# Sheet2.net
KiCad netlist of a schematic drawn in Altium Designer
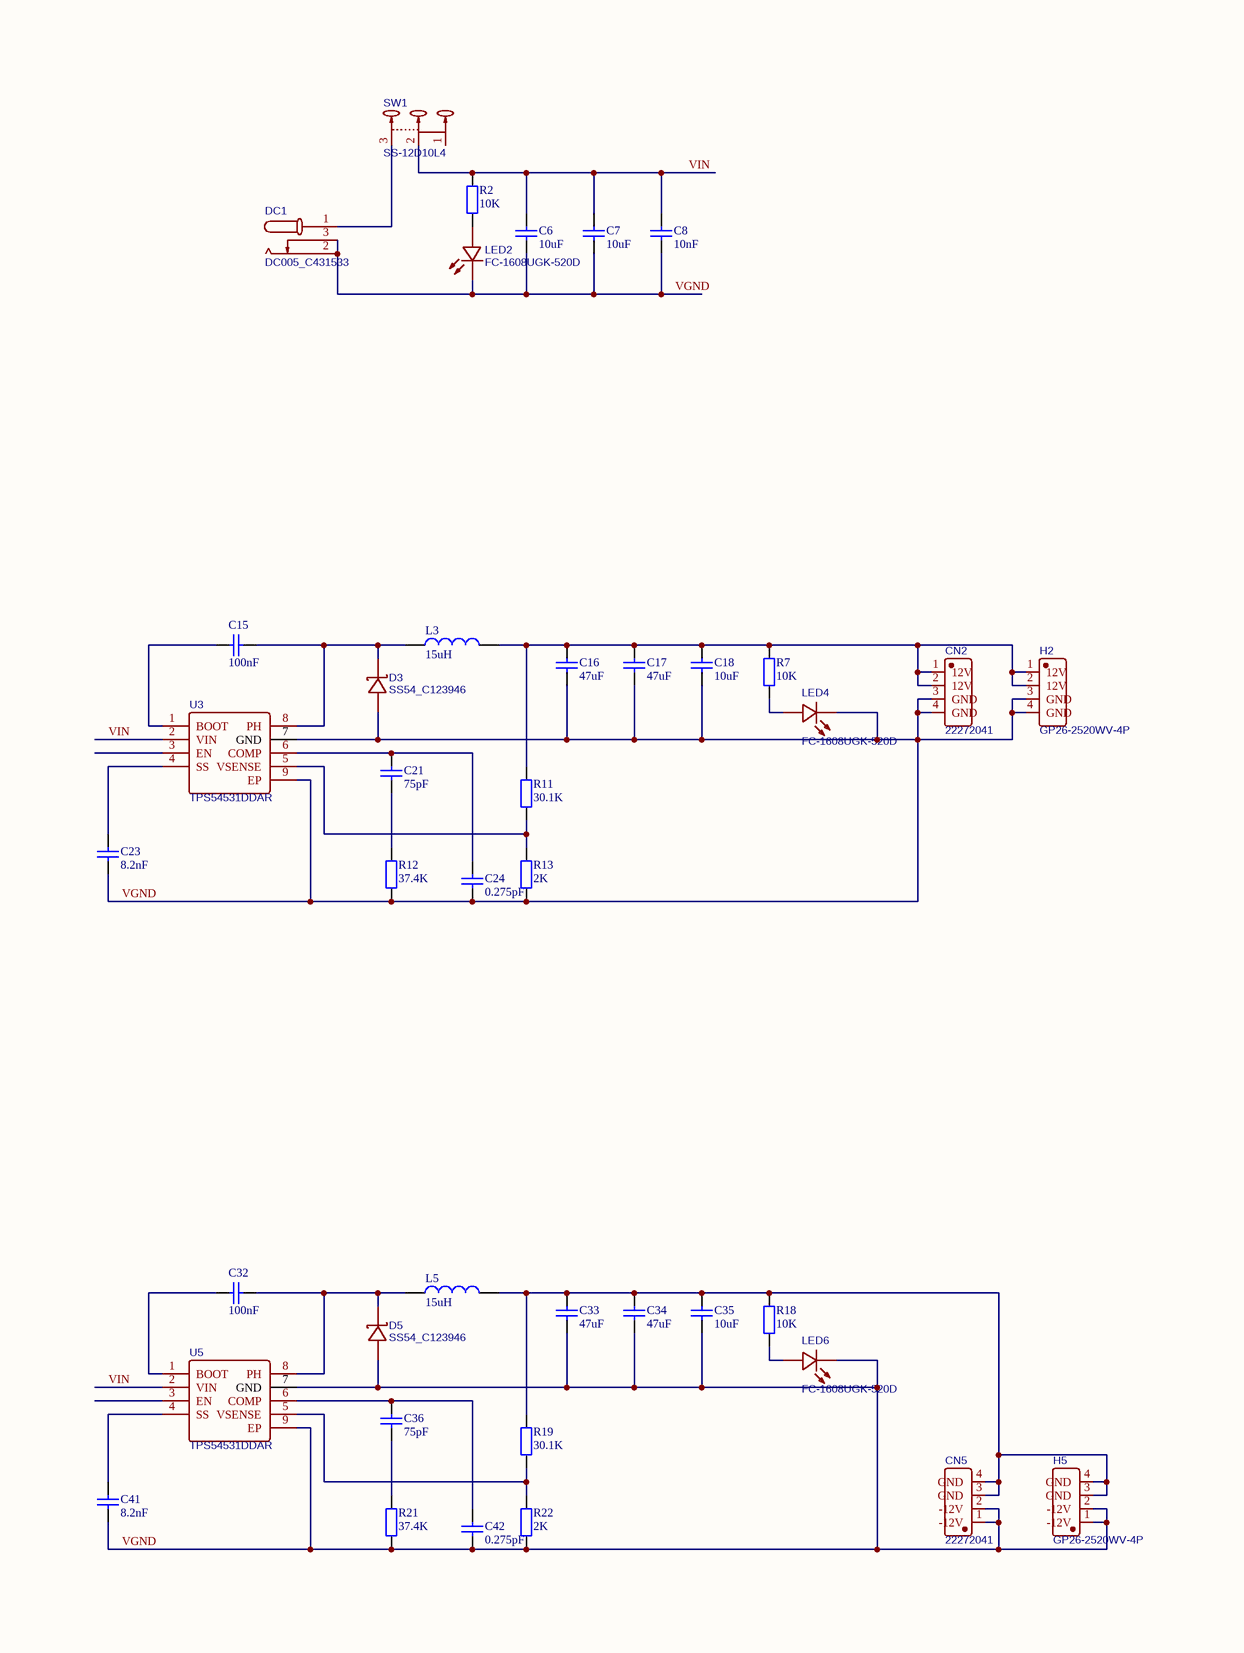
[diagram p0: Sheet2.SchDoc, left]
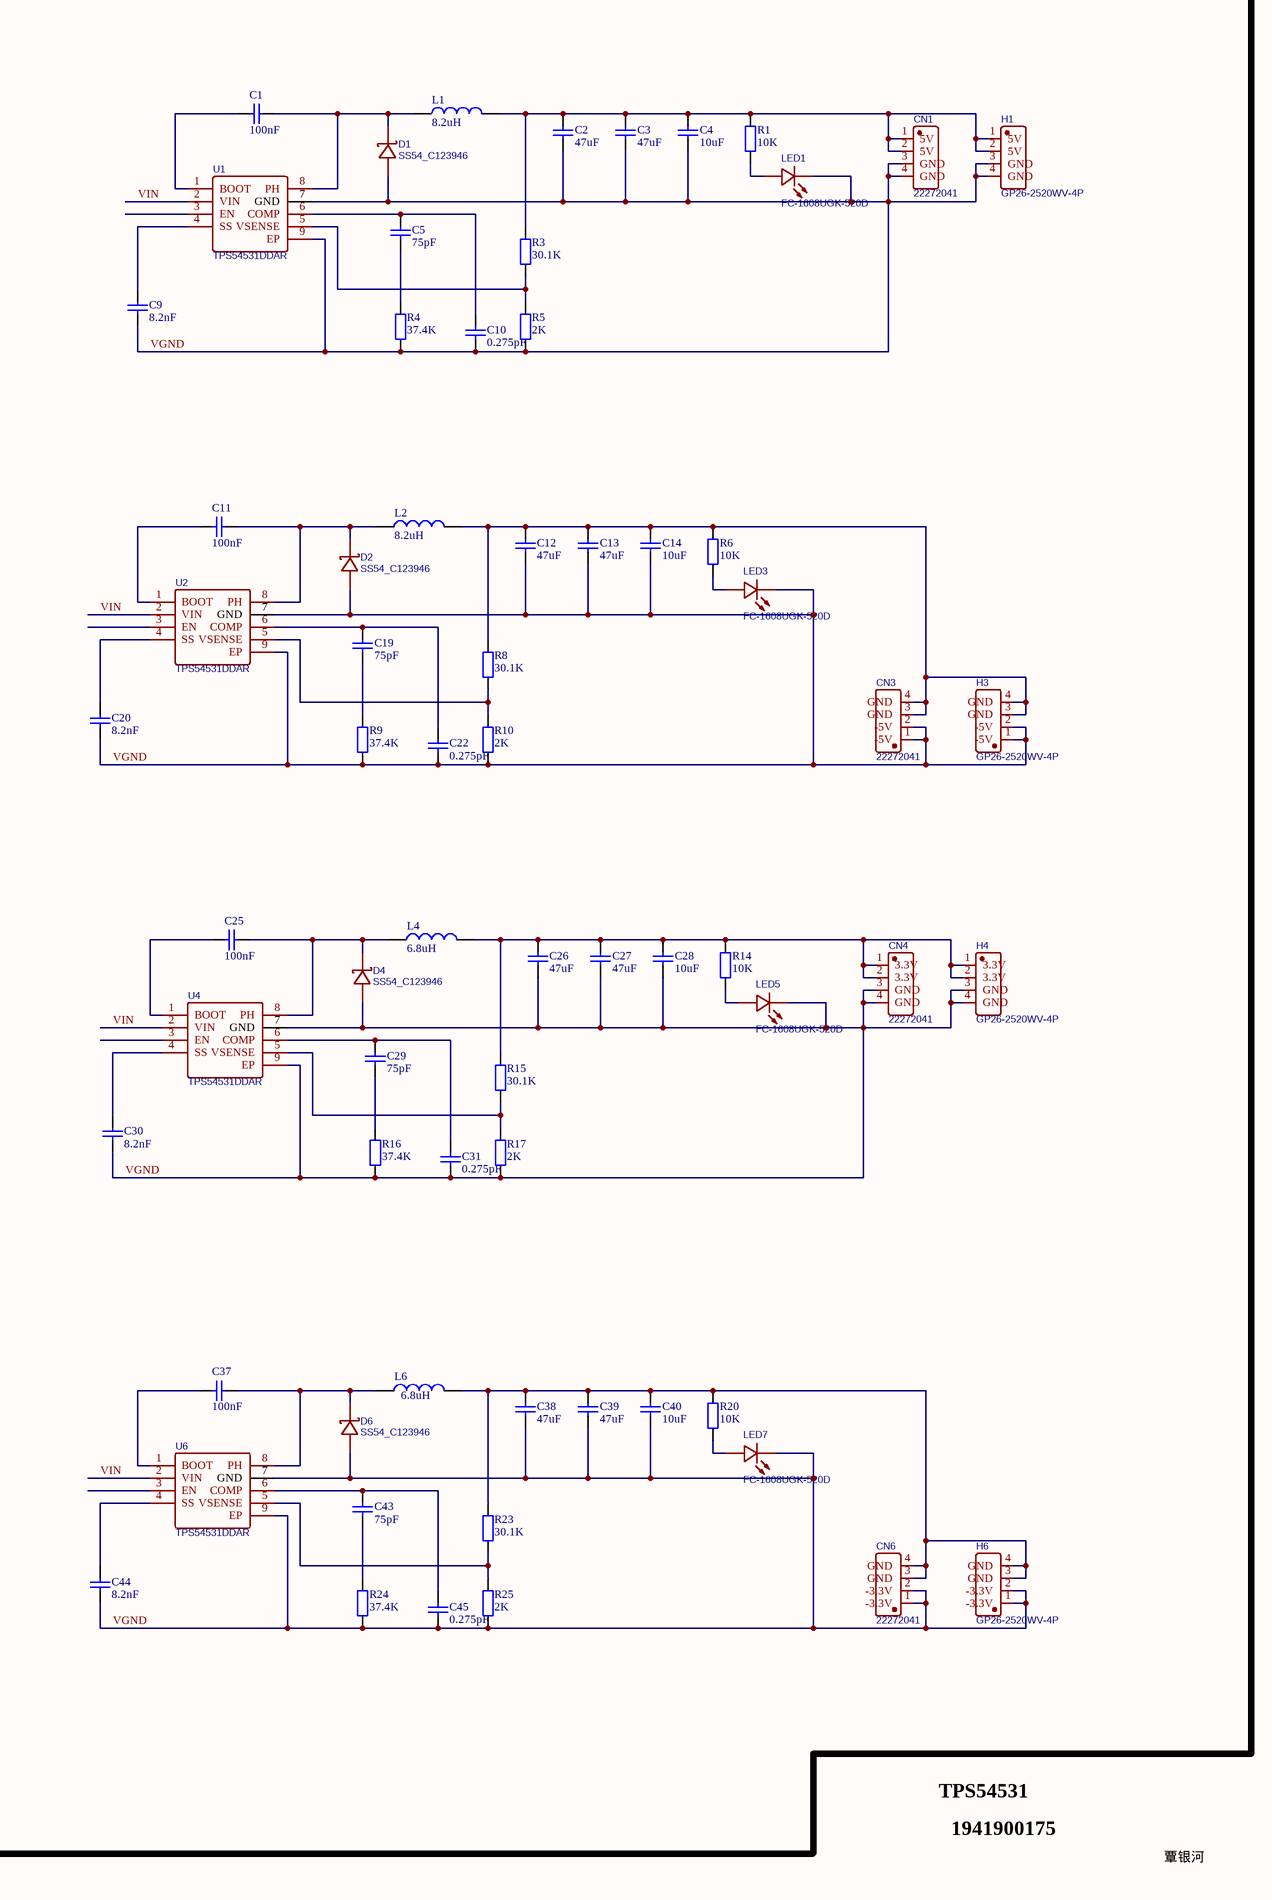
[diagram p1: Sheet2.SchDoc, right]

(export (version "E")
  (design (tool "Eeschema 10.0.6"))
  (components
    (comp (ref "C1")
      (value "100nF")
      (footprint "C0603_M")
      (description "贴片电容")
      (libsource (lib "0.1 - 电阻-电容-电感-磁珠-电位器") (part "C"))
    )
    (comp (ref "C2")
      (value "47uF")
      (footprint "C0603_M")
      (description "贴片电容")
      (libsource (lib "0.1 - 电阻-电容-电感-磁珠-电位器") (part "C"))
    )
    (comp (ref "C3")
      (value "47uF")
      (footprint "C0603_M")
      (description "贴片电容")
      (libsource (lib "0.1 - 电阻-电容-电感-磁珠-电位器") (part "C"))
    )
    (comp (ref "C4")
      (value "10uF")
      (footprint "C0603_M")
      (description "贴片电容")
      (libsource (lib "0.1 - 电阻-电容-电感-磁珠-电位器") (part "C"))
    )
    (comp (ref "C5")
      (value "75pF")
      (footprint "C0603_M")
      (description "贴片电容")
      (libsource (lib "0.1 - 电阻-电容-电感-磁珠-电位器") (part "C"))
    )
    (comp (ref "C6")
      (value "10uF")
      (footprint "C0603_M")
      (description "贴片电容")
      (libsource (lib "0.1 - 电阻-电容-电感-磁珠-电位器") (part "C"))
    )
    (comp (ref "C7")
      (value "10uF")
      (footprint "C0603_M")
      (description "贴片电容")
      (libsource (lib "0.1 - 电阻-电容-电感-磁珠-电位器") (part "C"))
    )
    (comp (ref "C8")
      (value "10nF")
      (footprint "C0603_M")
      (description "贴片电容")
      (libsource (lib "0.1 - 电阻-电容-电感-磁珠-电位器") (part "C"))
    )
    (comp (ref "C9")
      (value "8.2nF")
      (footprint "C0603_M")
      (description "贴片电容")
      (libsource (lib "0.1 - 电阻-电容-电感-磁珠-电位器") (part "C"))
    )
    (comp (ref "C10")
      (value "0.275pF")
      (footprint "C0603_M")
      (description "贴片电容")
      (libsource (lib "0.1 - 电阻-电容-电感-磁珠-电位器") (part "C"))
    )
    (comp (ref "C11")
      (value "100nF")
      (footprint "C0603_M")
      (description "贴片电容")
      (libsource (lib "0.1 - 电阻-电容-电感-磁珠-电位器") (part "C"))
    )
    (comp (ref "C12")
      (value "47uF")
      (footprint "C0603_M")
      (description "贴片电容")
      (libsource (lib "0.1 - 电阻-电容-电感-磁珠-电位器") (part "C"))
    )
    (comp (ref "C13")
      (value "47uF")
      (footprint "C0603_M")
      (description "贴片电容")
      (libsource (lib "0.1 - 电阻-电容-电感-磁珠-电位器") (part "C"))
    )
    (comp (ref "C14")
      (value "10uF")
      (footprint "C0603_M")
      (description "贴片电容")
      (libsource (lib "0.1 - 电阻-电容-电感-磁珠-电位器") (part "C"))
    )
    (comp (ref "C15")
      (value "100nF")
      (footprint "C0603_M")
      (description "贴片电容")
      (libsource (lib "0.1 - 电阻-电容-电感-磁珠-电位器") (part "C"))
    )
    (comp (ref "C16")
      (value "47uF")
      (footprint "C0603_M")
      (description "贴片电容")
      (libsource (lib "0.1 - 电阻-电容-电感-磁珠-电位器") (part "C"))
    )
    (comp (ref "C17")
      (value "47uF")
      (footprint "C0603_M")
      (description "贴片电容")
      (libsource (lib "0.1 - 电阻-电容-电感-磁珠-电位器") (part "C"))
    )
    (comp (ref "C18")
      (value "10uF")
      (footprint "C0603_M")
      (description "贴片电容")
      (libsource (lib "0.1 - 电阻-电容-电感-磁珠-电位器") (part "C"))
    )
    (comp (ref "C19")
      (value "75pF")
      (footprint "C0603_M")
      (description "贴片电容")
      (libsource (lib "0.1 - 电阻-电容-电感-磁珠-电位器") (part "C"))
    )
    (comp (ref "C20")
      (value "8.2nF")
      (footprint "C0603_M")
      (description "贴片电容")
      (libsource (lib "0.1 - 电阻-电容-电感-磁珠-电位器") (part "C"))
    )
    (comp (ref "C21")
      (value "75pF")
      (footprint "C0603_M")
      (description "贴片电容")
      (libsource (lib "0.1 - 电阻-电容-电感-磁珠-电位器") (part "C"))
    )
    (comp (ref "C22")
      (value "0.275pF")
      (footprint "C0603_M")
      (description "贴片电容")
      (libsource (lib "0.1 - 电阻-电容-电感-磁珠-电位器") (part "C"))
    )
    (comp (ref "C23")
      (value "8.2nF")
      (footprint "C0603_M")
      (description "贴片电容")
      (libsource (lib "0.1 - 电阻-电容-电感-磁珠-电位器") (part "C"))
    )
    (comp (ref "C24")
      (value "0.275pF")
      (footprint "C0603_M")
      (description "贴片电容")
      (libsource (lib "0.1 - 电阻-电容-电感-磁珠-电位器") (part "C"))
    )
    (comp (ref "C25")
      (value "100nF")
      (footprint "C0603_M")
      (description "贴片电容")
      (libsource (lib "0.1 - 电阻-电容-电感-磁珠-电位器") (part "C"))
    )
    (comp (ref "C26")
      (value "47uF")
      (footprint "C0603_M")
      (description "贴片电容")
      (libsource (lib "0.1 - 电阻-电容-电感-磁珠-电位器") (part "C"))
    )
    (comp (ref "C27")
      (value "47uF")
      (footprint "C0603_M")
      (description "贴片电容")
      (libsource (lib "0.1 - 电阻-电容-电感-磁珠-电位器") (part "C"))
    )
    (comp (ref "C28")
      (value "10uF")
      (footprint "C0603_M")
      (description "贴片电容")
      (libsource (lib "0.1 - 电阻-电容-电感-磁珠-电位器") (part "C"))
    )
    (comp (ref "C29")
      (value "75pF")
      (footprint "C0603_M")
      (description "贴片电容")
      (libsource (lib "0.1 - 电阻-电容-电感-磁珠-电位器") (part "C"))
    )
    (comp (ref "C30")
      (value "8.2nF")
      (footprint "C0603_M")
      (description "贴片电容")
      (libsource (lib "0.1 - 电阻-电容-电感-磁珠-电位器") (part "C"))
    )
    (comp (ref "C31")
      (value "0.275pF")
      (footprint "C0603_M")
      (description "贴片电容")
      (libsource (lib "0.1 - 电阻-电容-电感-磁珠-电位器") (part "C"))
    )
    (comp (ref "C32")
      (value "100nF")
      (footprint "C0603_M")
      (description "贴片电容")
      (libsource (lib "0.1 - 电阻-电容-电感-磁珠-电位器") (part "C"))
    )
    (comp (ref "C33")
      (value "47uF")
      (footprint "C0603_M")
      (description "贴片电容")
      (libsource (lib "0.1 - 电阻-电容-电感-磁珠-电位器") (part "C"))
    )
    (comp (ref "C34")
      (value "47uF")
      (footprint "C0603_M")
      (description "贴片电容")
      (libsource (lib "0.1 - 电阻-电容-电感-磁珠-电位器") (part "C"))
    )
    (comp (ref "C35")
      (value "10uF")
      (footprint "C0603_M")
      (description "贴片电容")
      (libsource (lib "0.1 - 电阻-电容-电感-磁珠-电位器") (part "C"))
    )
    (comp (ref "C36")
      (value "75pF")
      (footprint "C0603_M")
      (description "贴片电容")
      (libsource (lib "0.1 - 电阻-电容-电感-磁珠-电位器") (part "C"))
    )
    (comp (ref "C37")
      (value "100nF")
      (footprint "C0603_M")
      (description "贴片电容")
      (libsource (lib "0.1 - 电阻-电容-电感-磁珠-电位器") (part "C"))
    )
    (comp (ref "C38")
      (value "47uF")
      (footprint "C0603_M")
      (description "贴片电容")
      (libsource (lib "0.1 - 电阻-电容-电感-磁珠-电位器") (part "C"))
    )
    (comp (ref "C39")
      (value "47uF")
      (footprint "C0603_M")
      (description "贴片电容")
      (libsource (lib "0.1 - 电阻-电容-电感-磁珠-电位器") (part "C"))
    )
    (comp (ref "C40")
      (value "10uF")
      (footprint "C0603_M")
      (description "贴片电容")
      (libsource (lib "0.1 - 电阻-电容-电感-磁珠-电位器") (part "C"))
    )
    (comp (ref "C41")
      (value "8.2nF")
      (footprint "C0603_M")
      (description "贴片电容")
      (libsource (lib "0.1 - 电阻-电容-电感-磁珠-电位器") (part "C"))
    )
    (comp (ref "C42")
      (value "0.275pF")
      (footprint "C0603_M")
      (description "贴片电容")
      (libsource (lib "0.1 - 电阻-电容-电感-磁珠-电位器") (part "C"))
    )
    (comp (ref "C43")
      (value "75pF")
      (footprint "C0603_M")
      (description "贴片电容")
      (libsource (lib "0.1 - 电阻-电容-电感-磁珠-电位器") (part "C"))
    )
    (comp (ref "C44")
      (value "8.2nF")
      (footprint "C0603_M")
      (description "贴片电容")
      (libsource (lib "0.1 - 电阻-电容-电感-磁珠-电位器") (part "C"))
    )
    (comp (ref "C45")
      (value "0.275pF")
      (footprint "C0603_M")
      (description "贴片电容")
      (libsource (lib "0.1 - 电阻-电容-电感-磁珠-电位器") (part "C"))
    )
    (comp (ref "CN1")
      (value "22272041")
      (footprint "CONN-TH_22272041")
      (fields (field (name "BOM_SUPPLIER PART") "C504991") (field (name "CONTRIBUTOR") "LCSC"))
      (libsource (lib "22272041") (part "22272041"))
    )
    (comp (ref "CN2")
      (value "22272041")
      (footprint "CONN-TH_22272041")
      (fields (field (name "BOM_SUPPLIER PART") "C504991") (field (name "CONTRIBUTOR") "LCSC"))
      (libsource (lib "22272041") (part "22272041"))
    )
    (comp (ref "CN3")
      (value "22272041")
      (footprint "CONN-TH_22272041")
      (fields (field (name "BOM_SUPPLIER PART") "C504991") (field (name "CONTRIBUTOR") "LCSC"))
      (libsource (lib "22272041") (part "22272041"))
    )
    (comp (ref "CN4")
      (value "22272041")
      (footprint "CONN-TH_22272041")
      (fields (field (name "BOM_SUPPLIER PART") "C504991") (field (name "CONTRIBUTOR") "LCSC"))
      (libsource (lib "22272041") (part "22272041"))
    )
    (comp (ref "CN5")
      (value "22272041")
      (footprint "CONN-TH_22272041")
      (fields (field (name "BOM_SUPPLIER PART") "C504991") (field (name "CONTRIBUTOR") "LCSC"))
      (libsource (lib "22272041") (part "22272041"))
    )
    (comp (ref "CN6")
      (value "22272041")
      (footprint "CONN-TH_22272041")
      (fields (field (name "BOM_SUPPLIER PART") "C504991") (field (name "CONTRIBUTOR") "LCSC"))
      (libsource (lib "22272041") (part "22272041"))
    )
    (comp (ref "D1")
      (value "SS54_C123946")
      (footprint "SMA_L4.4-W2.8-LS5.4-RD")
      (fields
        (field (name "BOM_SUPPLIER PART") "C123946")
        (field (name "BOM_MANUFACTURER PART") "SS54")
        (field (name "CONTRIBUTOR") "LCSC")
      )
      (libsource (lib "ss54 C123946") (part "SS54_C123946"))
    )
    (comp (ref "D2")
      (value "SS54_C123946")
      (footprint "SMA_L4.4-W2.8-LS5.4-RD")
      (fields
        (field (name "BOM_SUPPLIER PART") "C123946")
        (field (name "BOM_MANUFACTURER PART") "SS54")
        (field (name "CONTRIBUTOR") "LCSC")
      )
      (libsource (lib "ss54 C123946") (part "SS54_C123946"))
    )
    (comp (ref "D3")
      (value "SS54_C123946")
      (footprint "SMA_L4.4-W2.8-LS5.4-RD")
      (fields
        (field (name "BOM_SUPPLIER PART") "C123946")
        (field (name "BOM_MANUFACTURER PART") "SS54")
        (field (name "CONTRIBUTOR") "LCSC")
      )
      (libsource (lib "ss54 C123946") (part "SS54_C123946"))
    )
    (comp (ref "D4")
      (value "SS54_C123946")
      (footprint "SMA_L4.4-W2.8-LS5.4-RD")
      (fields
        (field (name "BOM_SUPPLIER PART") "C123946")
        (field (name "BOM_MANUFACTURER PART") "SS54")
        (field (name "CONTRIBUTOR") "LCSC")
      )
      (libsource (lib "ss54 C123946") (part "SS54_C123946"))
    )
    (comp (ref "D5")
      (value "SS54_C123946")
      (footprint "SMA_L4.4-W2.8-LS5.4-RD")
      (fields
        (field (name "BOM_SUPPLIER PART") "C123946")
        (field (name "BOM_MANUFACTURER PART") "SS54")
        (field (name "CONTRIBUTOR") "LCSC")
      )
      (libsource (lib "ss54 C123946") (part "SS54_C123946"))
    )
    (comp (ref "D6")
      (value "SS54_C123946")
      (footprint "SMA_L4.4-W2.8-LS5.4-RD")
      (fields
        (field (name "BOM_SUPPLIER PART") "C123946")
        (field (name "BOM_MANUFACTURER PART") "SS54")
        (field (name "CONTRIBUTOR") "LCSC")
      )
      (libsource (lib "ss54 C123946") (part "SS54_C123946"))
    )
    (comp (ref "DC1")
      (value "DC005_C431533")
      (footprint "DC-IN-TH_DC005")
      (fields
        (field (name "BOM_SUPPLIER PART") "C431533")
        (field (name "BOM_MANUFACTURER PART") "DC005")
        (field (name "CONTRIBUTOR") "LCSC")
      )
      (libsource (lib "DC005") (part "DC005_C431533"))
    )
    (comp (ref "H1")
      (value "GP26-2520WV-4P")
      (footprint "HDR-TH_4P-P2.54-V-F-R1-C4")
      (fields (field (name "BOM_SUPPLIER PART") "C2681739") (field (name "CONTRIBUTOR") "LCSC"))
      (libsource (lib "gp26-2520wv-4p") (part "GP26-2520WV-4P"))
    )
    (comp (ref "H2")
      (value "GP26-2520WV-4P")
      (footprint "HDR-TH_4P-P2.54-V-F-R1-C4")
      (fields (field (name "BOM_SUPPLIER PART") "C2681739") (field (name "CONTRIBUTOR") "LCSC"))
      (libsource (lib "gp26-2520wv-4p") (part "GP26-2520WV-4P"))
    )
    (comp (ref "H3")
      (value "GP26-2520WV-4P")
      (footprint "HDR-TH_4P-P2.54-V-F-R1-C4")
      (fields (field (name "BOM_SUPPLIER PART") "C2681739") (field (name "CONTRIBUTOR") "LCSC"))
      (libsource (lib "gp26-2520wv-4p") (part "GP26-2520WV-4P"))
    )
    (comp (ref "H4")
      (value "GP26-2520WV-4P")
      (footprint "HDR-TH_4P-P2.54-V-F-R1-C4")
      (fields (field (name "BOM_SUPPLIER PART") "C2681739") (field (name "CONTRIBUTOR") "LCSC"))
      (libsource (lib "gp26-2520wv-4p") (part "GP26-2520WV-4P"))
    )
    (comp (ref "H5")
      (value "GP26-2520WV-4P")
      (footprint "HDR-TH_4P-P2.54-V-F-R1-C4")
      (fields (field (name "BOM_SUPPLIER PART") "C2681739") (field (name "CONTRIBUTOR") "LCSC"))
      (libsource (lib "gp26-2520wv-4p") (part "GP26-2520WV-4P"))
    )
    (comp (ref "H6")
      (value "GP26-2520WV-4P")
      (footprint "HDR-TH_4P-P2.54-V-F-R1-C4")
      (fields (field (name "BOM_SUPPLIER PART") "C2681739") (field (name "CONTRIBUTOR") "LCSC"))
      (libsource (lib "gp26-2520wv-4p") (part "GP26-2520WV-4P"))
    )
    (comp (ref "L1")
      (value "8.2uH")
      (footprint "IND-SMD_L7.0-W6.6")
      (description "色环电感")
      (libsource (lib "0.1 - 电阻-电容-电感-磁珠-电位器") (part "L-AL"))
    )
    (comp (ref "L2")
      (value "8.2uH")
      (footprint "IND-SMD_L7.0-W6.6")
      (description "色环电感")
      (libsource (lib "0.1 - 电阻-电容-电感-磁珠-电位器") (part "L-AL"))
    )
    (comp (ref "L3")
      (value "15uH")
      (footprint "IND-SMD_L5.0-W5.0_SWPA5040S")
      (description "色环电感")
      (libsource (lib "0.1 - 电阻-电容-电感-磁珠-电位器") (part "L-AL"))
    )
    (comp (ref "L4")
      (value "6.8uH")
      (footprint "IND-SMD_L10.5-W10.3")
      (description "色环电感")
      (libsource (lib "0.1 - 电阻-电容-电感-磁珠-电位器") (part "L-AL"))
    )
    (comp (ref "L5")
      (value "15uH")
      (footprint "IND-SMD_L5.0-W5.0_SWPA5040S")
      (description "色环电感")
      (libsource (lib "0.1 - 电阻-电容-电感-磁珠-电位器") (part "L-AL"))
    )
    (comp (ref "L6")
      (value "6.8uH")
      (footprint "IND-SMD_L10.5-W10.3")
      (description "色环电感")
      (libsource (lib "0.1 - 电阻-电容-电感-磁珠-电位器") (part "L-AL"))
    )
    (comp (ref "LED1")
      (value "FC-1608UGK-520D")
      (footprint "LED0603-RD")
      (fields (field (name "BOM_SUPPLIER PART") "C87326"))
      (libsource (lib "fc-1608ugk-520d") (part "FC-1608UGK-520D"))
    )
    (comp (ref "LED2")
      (value "FC-1608UGK-520D")
      (footprint "LED0603-RD")
      (fields (field (name "BOM_SUPPLIER PART") "C87326"))
      (libsource (lib "fc-1608ugk-520d") (part "FC-1608UGK-520D"))
    )
    (comp (ref "LED3")
      (value "FC-1608UGK-520D")
      (footprint "LED0603-RD")
      (fields (field (name "BOM_SUPPLIER PART") "C87326"))
      (libsource (lib "fc-1608ugk-520d") (part "FC-1608UGK-520D"))
    )
    (comp (ref "LED4")
      (value "FC-1608UGK-520D")
      (footprint "LED0603-RD")
      (fields (field (name "BOM_SUPPLIER PART") "C87326"))
      (libsource (lib "fc-1608ugk-520d") (part "FC-1608UGK-520D"))
    )
    (comp (ref "LED5")
      (value "FC-1608UGK-520D")
      (footprint "LED0603-RD")
      (fields (field (name "BOM_SUPPLIER PART") "C87326"))
      (libsource (lib "fc-1608ugk-520d") (part "FC-1608UGK-520D"))
    )
    (comp (ref "LED6")
      (value "FC-1608UGK-520D")
      (footprint "LED0603-RD")
      (fields (field (name "BOM_SUPPLIER PART") "C87326"))
      (libsource (lib "fc-1608ugk-520d") (part "FC-1608UGK-520D"))
    )
    (comp (ref "LED7")
      (value "FC-1608UGK-520D")
      (footprint "LED0603-RD")
      (fields (field (name "BOM_SUPPLIER PART") "C87326"))
      (libsource (lib "fc-1608ugk-520d") (part "FC-1608UGK-520D"))
    )
    (comp (ref "R1")
      (value "10K")
      (footprint "R0603_M")
      (description "贴片电阻")
      (libsource (lib "0.1 - 电阻-电容-电感-磁珠-电位器") (part "R"))
    )
    (comp (ref "R2")
      (value "10K")
      (footprint "R0603_M")
      (description "贴片电阻")
      (libsource (lib "0.1 - 电阻-电容-电感-磁珠-电位器") (part "R"))
    )
    (comp (ref "R3")
      (value "30.1K")
      (footprint "R0603_M")
      (description "贴片电阻")
      (libsource (lib "0.1 - 电阻-电容-电感-磁珠-电位器") (part "R"))
    )
    (comp (ref "R4")
      (value "37.4K")
      (footprint "R0603_M")
      (description "贴片电阻")
      (libsource (lib "0.1 - 电阻-电容-电感-磁珠-电位器") (part "R"))
    )
    (comp (ref "R5")
      (value "2K")
      (footprint "R0603_M")
      (description "贴片电阻")
      (libsource (lib "0.1 - 电阻-电容-电感-磁珠-电位器") (part "R"))
    )
    (comp (ref "R6")
      (value "10K")
      (footprint "R0603_M")
      (description "贴片电阻")
      (libsource (lib "0.1 - 电阻-电容-电感-磁珠-电位器") (part "R"))
    )
    (comp (ref "R7")
      (value "10K")
      (footprint "R0603_M")
      (description "贴片电阻")
      (libsource (lib "0.1 - 电阻-电容-电感-磁珠-电位器") (part "R"))
    )
    (comp (ref "R8")
      (value "30.1K")
      (footprint "R0603_M")
      (description "贴片电阻")
      (libsource (lib "0.1 - 电阻-电容-电感-磁珠-电位器") (part "R"))
    )
    (comp (ref "R9")
      (value "37.4K")
      (footprint "R0603_M")
      (description "贴片电阻")
      (libsource (lib "0.1 - 电阻-电容-电感-磁珠-电位器") (part "R"))
    )
    (comp (ref "R10")
      (value "2K")
      (footprint "R0603_M")
      (description "贴片电阻")
      (libsource (lib "0.1 - 电阻-电容-电感-磁珠-电位器") (part "R"))
    )
    (comp (ref "R11")
      (value "30.1K")
      (footprint "R0603_M")
      (description "贴片电阻")
      (libsource (lib "0.1 - 电阻-电容-电感-磁珠-电位器") (part "R"))
    )
    (comp (ref "R12")
      (value "37.4K")
      (footprint "R0603_M")
      (description "贴片电阻")
      (libsource (lib "0.1 - 电阻-电容-电感-磁珠-电位器") (part "R"))
    )
    (comp (ref "R13")
      (value "2K")
      (footprint "R0603_M")
      (description "贴片电阻")
      (libsource (lib "0.1 - 电阻-电容-电感-磁珠-电位器") (part "R"))
    )
    (comp (ref "R14")
      (value "10K")
      (footprint "R0603_M")
      (description "贴片电阻")
      (libsource (lib "0.1 - 电阻-电容-电感-磁珠-电位器") (part "R"))
    )
    (comp (ref "R15")
      (value "30.1K")
      (footprint "R0603_M")
      (description "贴片电阻")
      (libsource (lib "0.1 - 电阻-电容-电感-磁珠-电位器") (part "R"))
    )
    (comp (ref "R16")
      (value "37.4K")
      (footprint "R0603_M")
      (description "贴片电阻")
      (libsource (lib "0.1 - 电阻-电容-电感-磁珠-电位器") (part "R"))
    )
    (comp (ref "R17")
      (value "2K")
      (footprint "R0603_M")
      (description "贴片电阻")
      (libsource (lib "0.1 - 电阻-电容-电感-磁珠-电位器") (part "R"))
    )
    (comp (ref "R18")
      (value "10K")
      (footprint "R0603_M")
      (description "贴片电阻")
      (libsource (lib "0.1 - 电阻-电容-电感-磁珠-电位器") (part "R"))
    )
    (comp (ref "R19")
      (value "30.1K")
      (footprint "R0603_M")
      (description "贴片电阻")
      (libsource (lib "0.1 - 电阻-电容-电感-磁珠-电位器") (part "R"))
    )
    (comp (ref "R20")
      (value "10K")
      (footprint "R0603_M")
      (description "贴片电阻")
      (libsource (lib "0.1 - 电阻-电容-电感-磁珠-电位器") (part "R"))
    )
    (comp (ref "R21")
      (value "37.4K")
      (footprint "R0603_M")
      (description "贴片电阻")
      (libsource (lib "0.1 - 电阻-电容-电感-磁珠-电位器") (part "R"))
    )
    (comp (ref "R22")
      (value "2K")
      (footprint "R0603_M")
      (description "贴片电阻")
      (libsource (lib "0.1 - 电阻-电容-电感-磁珠-电位器") (part "R"))
    )
    (comp (ref "R23")
      (value "30.1K")
      (footprint "R0603_M")
      (description "贴片电阻")
      (libsource (lib "0.1 - 电阻-电容-电感-磁珠-电位器") (part "R"))
    )
    (comp (ref "R24")
      (value "37.4K")
      (footprint "R0603_M")
      (description "贴片电阻")
      (libsource (lib "0.1 - 电阻-电容-电感-磁珠-电位器") (part "R"))
    )
    (comp (ref "R25")
      (value "2K")
      (footprint "R0603_M")
      (description "贴片电阻")
      (libsource (lib "0.1 - 电阻-电容-电感-磁珠-电位器") (part "R"))
    )
    (comp (ref "SW1")
      (value "SS-12D10L4")
      (footprint "SW-TH_SS-12D10L3")
      (fields (field (name "BOM_SUPPLIER PART") "C843364") (field (name "CONTRIBUTOR") "LCSC"))
      (libsource (lib "SS-12D10L4") (part "SS-12D10L4"))
    )
    (comp (ref "U1")
      (value "TPS54531DDAR")
      (footprint "SOIC-8_L5.0-W4.0-P1.27-LS6.0-BL-EP")
      (fields (field (name "BOM_SUPPLIER PART") "C50605"))
      (libsource (lib "TPS54531DDAR") (part "TPS54531DDAR"))
    )
    (comp (ref "U2")
      (value "TPS54531DDAR")
      (footprint "SOIC-8_L5.0-W4.0-P1.27-LS6.0-BL-EP")
      (fields (field (name "BOM_SUPPLIER PART") "C50605"))
      (libsource (lib "TPS54531DDAR") (part "TPS54531DDAR"))
    )
    (comp (ref "U3")
      (value "TPS54531DDAR")
      (footprint "SOIC-8_L5.0-W4.0-P1.27-LS6.0-BL-EP")
      (fields (field (name "BOM_SUPPLIER PART") "C50605"))
      (libsource (lib "TPS54531DDAR") (part "TPS54531DDAR"))
    )
    (comp (ref "U4")
      (value "TPS54531DDAR")
      (footprint "SOIC-8_L5.0-W4.0-P1.27-LS6.0-BL-EP")
      (fields (field (name "BOM_SUPPLIER PART") "C50605"))
      (libsource (lib "TPS54531DDAR") (part "TPS54531DDAR"))
    )
    (comp (ref "U5")
      (value "TPS54531DDAR")
      (footprint "SOIC-8_L5.0-W4.0-P1.27-LS6.0-BL-EP")
      (fields (field (name "BOM_SUPPLIER PART") "C50605"))
      (libsource (lib "TPS54531DDAR") (part "TPS54531DDAR"))
    )
    (comp (ref "U6")
      (value "TPS54531DDAR")
      (footprint "SOIC-8_L5.0-W4.0-P1.27-LS6.0-BL-EP")
      (fields (field (name "BOM_SUPPLIER PART") "C50605"))
      (libsource (lib "TPS54531DDAR") (part "TPS54531DDAR"))
    )
  )
  (nets
    (net (code "1") (name "/VGND") (class "Default")
      (node (ref "C10") (pin "1") (pinfunction "1_1") (pintype "passive"))
      (node (ref "C12") (pin "1") (pinfunction "1_1") (pintype "passive"))
      (node (ref "C13") (pin "1") (pinfunction "1_1") (pintype "passive"))
      (node (ref "C14") (pin "1") (pinfunction "1_1") (pintype "passive"))
      (node (ref "C16") (pin "1") (pinfunction "1_1") (pintype "passive"))
      (node (ref "C17") (pin "1") (pinfunction "1_1") (pintype "passive"))
      (node (ref "C18") (pin "1") (pinfunction "1_1") (pintype "passive"))
      (node (ref "C2") (pin "1") (pinfunction "1_1") (pintype "passive"))
      (node (ref "C20") (pin "1") (pinfunction "1_1") (pintype "passive"))
      (node (ref "C22") (pin "1") (pinfunction "1_1") (pintype "passive"))
      (node (ref "C23") (pin "1") (pinfunction "1_1") (pintype "passive"))
      (node (ref "C24") (pin "1") (pinfunction "1_1") (pintype "passive"))
      (node (ref "C26") (pin "1") (pinfunction "1_1") (pintype "passive"))
      (node (ref "C27") (pin "1") (pinfunction "1_1") (pintype "passive"))
      (node (ref "C28") (pin "1") (pinfunction "1_1") (pintype "passive"))
      (node (ref "C3") (pin "1") (pinfunction "1_1") (pintype "passive"))
      (node (ref "C30") (pin "1") (pinfunction "1_1") (pintype "passive"))
      (node (ref "C31") (pin "1") (pinfunction "1_1") (pintype "passive"))
      (node (ref "C33") (pin "1") (pinfunction "1_1") (pintype "passive"))
      (node (ref "C34") (pin "1") (pinfunction "1_1") (pintype "passive"))
      (node (ref "C35") (pin "1") (pinfunction "1_1") (pintype "passive"))
      (node (ref "C38") (pin "1") (pinfunction "1_1") (pintype "passive"))
      (node (ref "C39") (pin "1") (pinfunction "1_1") (pintype "passive"))
      (node (ref "C4") (pin "1") (pinfunction "1_1") (pintype "passive"))
      (node (ref "C40") (pin "1") (pinfunction "1_1") (pintype "passive"))
      (node (ref "C41") (pin "1") (pinfunction "1_1") (pintype "passive"))
      (node (ref "C42") (pin "1") (pinfunction "1_1") (pintype "passive"))
      (node (ref "C44") (pin "1") (pinfunction "1_1") (pintype "passive"))
      (node (ref "C45") (pin "1") (pinfunction "1_1") (pintype "passive"))
      (node (ref "C6") (pin "1") (pinfunction "1_1") (pintype "passive"))
      (node (ref "C7") (pin "1") (pinfunction "1_1") (pintype "passive"))
      (node (ref "C8") (pin "1") (pinfunction "1_1") (pintype "passive"))
      (node (ref "C9") (pin "1") (pinfunction "1_1") (pintype "passive"))
      (node (ref "CN1") (pin "3") (pinfunction "GND_3") (pintype "passive"))
      (node (ref "CN1") (pin "4") (pinfunction "GND_4") (pintype "passive"))
      (node (ref "CN2") (pin "3") (pinfunction "GND_3") (pintype "passive"))
      (node (ref "CN2") (pin "4") (pinfunction "GND_4") (pintype "passive"))
      (node (ref "CN3") (pin "1") (pinfunction "5V_1") (pintype "passive"))
      (node (ref "CN3") (pin "2") (pinfunction "5V_2") (pintype "passive"))
      (node (ref "CN4") (pin "3") (pinfunction "GND_3") (pintype "passive"))
      (node (ref "CN4") (pin "4") (pinfunction "GND_4") (pintype "passive"))
      (node (ref "CN5") (pin "1") (pinfunction "5V_1") (pintype "passive"))
      (node (ref "CN5") (pin "2") (pinfunction "5V_2") (pintype "passive"))
      (node (ref "CN6") (pin "1") (pinfunction "5V_1") (pintype "passive"))
      (node (ref "CN6") (pin "2") (pinfunction "5V_2") (pintype "passive"))
      (node (ref "D1") (pin "2") (pinfunction "A_2") (pintype "passive"))
      (node (ref "D2") (pin "2") (pinfunction "A_2") (pintype "passive"))
      (node (ref "D3") (pin "2") (pinfunction "A_2") (pintype "passive"))
      (node (ref "D4") (pin "2") (pinfunction "A_2") (pintype "passive"))
      (node (ref "D5") (pin "2") (pinfunction "A_2") (pintype "passive"))
      (node (ref "D6") (pin "2") (pinfunction "A_2") (pintype "passive"))
      (node (ref "DC1") (pin "2") (pinfunction "2_2") (pintype "passive"))
      (node (ref "DC1") (pin "3") (pinfunction "3_3") (pintype "passive"))
      (node (ref "H1") (pin "3") (pinfunction "GND_3") (pintype "passive"))
      (node (ref "H1") (pin "4") (pinfunction "GND_4") (pintype "passive"))
      (node (ref "H2") (pin "3") (pinfunction "GND_3") (pintype "passive"))
      (node (ref "H2") (pin "4") (pinfunction "GND_4") (pintype "passive"))
      (node (ref "H3") (pin "1") (pinfunction "-3.3V_1") (pintype "passive"))
      (node (ref "H3") (pin "2") (pinfunction "-3.3V_2") (pintype "passive"))
      (node (ref "H4") (pin "3") (pinfunction "GND_3") (pintype "passive"))
      (node (ref "H4") (pin "4") (pinfunction "GND_4") (pintype "passive"))
      (node (ref "H5") (pin "1") (pinfunction "-3.3V_1") (pintype "passive"))
      (node (ref "H5") (pin "2") (pinfunction "-3.3V_2") (pintype "passive"))
      (node (ref "H6") (pin "1") (pinfunction "-3.3V_1") (pintype "passive"))
      (node (ref "H6") (pin "2") (pinfunction "-3.3V_2") (pintype "passive"))
      (node (ref "LED1") (pin "1") (pinfunction "K_1") (pintype "passive"))
      (node (ref "LED2") (pin "1") (pinfunction "K_1") (pintype "passive"))
      (node (ref "LED3") (pin "1") (pinfunction "K_1") (pintype "passive"))
      (node (ref "LED4") (pin "1") (pinfunction "K_1") (pintype "passive"))
      (node (ref "LED5") (pin "1") (pinfunction "K_1") (pintype "passive"))
      (node (ref "LED6") (pin "1") (pinfunction "K_1") (pintype "passive"))
      (node (ref "LED7") (pin "1") (pinfunction "K_1") (pintype "passive"))
      (node (ref "R10") (pin "1") (pinfunction "1_1") (pintype "passive"))
      (node (ref "R12") (pin "1") (pinfunction "1_1") (pintype "passive"))
      (node (ref "R13") (pin "1") (pinfunction "1_1") (pintype "passive"))
      (node (ref "R16") (pin "1") (pinfunction "1_1") (pintype "passive"))
      (node (ref "R17") (pin "1") (pinfunction "1_1") (pintype "passive"))
      (node (ref "R21") (pin "1") (pinfunction "1_1") (pintype "passive"))
      (node (ref "R22") (pin "1") (pinfunction "1_1") (pintype "passive"))
      (node (ref "R24") (pin "1") (pinfunction "1_1") (pintype "passive"))
      (node (ref "R25") (pin "1") (pinfunction "1_1") (pintype "passive"))
      (node (ref "R4") (pin "1") (pinfunction "1_1") (pintype "passive"))
      (node (ref "R5") (pin "1") (pinfunction "1_1") (pintype "passive"))
      (node (ref "R9") (pin "1") (pinfunction "1_1") (pintype "passive"))
      (node (ref "U1") (pin "7") (pinfunction "GND_7") (pintype "passive"))
      (node (ref "U1") (pin "9") (pinfunction "EP_9") (pintype "passive"))
      (node (ref "U2") (pin "7") (pinfunction "GND_7") (pintype "passive"))
      (node (ref "U2") (pin "9") (pinfunction "EP_9") (pintype "passive"))
      (node (ref "U3") (pin "7") (pinfunction "GND_7") (pintype "passive"))
      (node (ref "U3") (pin "9") (pinfunction "EP_9") (pintype "passive"))
      (node (ref "U4") (pin "7") (pinfunction "GND_7") (pintype "passive"))
      (node (ref "U4") (pin "9") (pinfunction "EP_9") (pintype "passive"))
      (node (ref "U5") (pin "7") (pinfunction "GND_7") (pintype "passive"))
      (node (ref "U5") (pin "9") (pinfunction "EP_9") (pintype "passive"))
      (node (ref "U6") (pin "7") (pinfunction "GND_7") (pintype "passive"))
      (node (ref "U6") (pin "9") (pinfunction "EP_9") (pintype "passive"))
    )
    (net (code "2") (name "/VIN") (class "Default")
      (node (ref "C6") (pin "2") (pinfunction "2_2") (pintype "passive"))
      (node (ref "C7") (pin "2") (pinfunction "2_2") (pintype "passive"))
      (node (ref "C8") (pin "2") (pinfunction "2_2") (pintype "passive"))
      (node (ref "R2") (pin "2") (pinfunction "2_2") (pintype "passive"))
      (node (ref "SW1") (pin "2") (pinfunction "2_2") (pintype "passive"))
      (node (ref "U1") (pin "2") (pinfunction "VIN_2") (pintype "passive"))
      (node (ref "U2") (pin "2") (pinfunction "VIN_2") (pintype "passive"))
      (node (ref "U3") (pin "2") (pinfunction "VIN_2") (pintype "passive"))
      (node (ref "U4") (pin "2") (pinfunction "VIN_2") (pintype "passive"))
      (node (ref "U5") (pin "2") (pinfunction "VIN_2") (pintype "passive"))
      (node (ref "U6") (pin "2") (pinfunction "VIN_2") (pintype "passive"))
    )
    (net (code "3") (name "Net-(C2-Pad2)") (class "Default")
      (node (ref "C2") (pin "2") (pinfunction "2_2") (pintype "passive"))
      (node (ref "C3") (pin "2") (pinfunction "2_2") (pintype "passive"))
      (node (ref "C4") (pin "2") (pinfunction "2_2") (pintype "passive"))
      (node (ref "CN1") (pin "1") (pinfunction "5V_1") (pintype "passive"))
      (node (ref "CN1") (pin "2") (pinfunction "5V_2") (pintype "passive"))
      (node (ref "H1") (pin "1") (pinfunction "-3.3V_1") (pintype "passive"))
      (node (ref "H1") (pin "2") (pinfunction "-3.3V_2") (pintype "passive"))
      (node (ref "L1") (pin "2") (pinfunction "2_2") (pintype "passive"))
      (node (ref "R1") (pin "2") (pinfunction "2_2") (pintype "passive"))
      (node (ref "R3") (pin "2") (pinfunction "2_2") (pintype "passive"))
    )
    (net (code "4") (name "Net-(C5-Pad1)") (class "Default")
      (node (ref "C5") (pin "1") (pinfunction "1_1") (pintype "passive"))
      (node (ref "R4") (pin "2") (pinfunction "2_2") (pintype "passive"))
    )
    (net (code "5") (name "Net-(C12-Pad2)") (class "Default")
      (node (ref "C12") (pin "2") (pinfunction "2_2") (pintype "passive"))
      (node (ref "C13") (pin "2") (pinfunction "2_2") (pintype "passive"))
      (node (ref "C14") (pin "2") (pinfunction "2_2") (pintype "passive"))
      (node (ref "CN3") (pin "3") (pinfunction "GND_3") (pintype "passive"))
      (node (ref "CN3") (pin "4") (pinfunction "GND_4") (pintype "passive"))
      (node (ref "H3") (pin "3") (pinfunction "GND_3") (pintype "passive"))
      (node (ref "H3") (pin "4") (pinfunction "GND_4") (pintype "passive"))
      (node (ref "L2") (pin "2") (pinfunction "2_2") (pintype "passive"))
      (node (ref "R6") (pin "2") (pinfunction "2_2") (pintype "passive"))
      (node (ref "R8") (pin "2") (pinfunction "2_2") (pintype "passive"))
    )
    (net (code "6") (name "Net-(C16-Pad2)") (class "Default")
      (node (ref "C16") (pin "2") (pinfunction "2_2") (pintype "passive"))
      (node (ref "C17") (pin "2") (pinfunction "2_2") (pintype "passive"))
      (node (ref "C18") (pin "2") (pinfunction "2_2") (pintype "passive"))
      (node (ref "CN2") (pin "1") (pinfunction "5V_1") (pintype "passive"))
      (node (ref "CN2") (pin "2") (pinfunction "5V_2") (pintype "passive"))
      (node (ref "H2") (pin "1") (pinfunction "-3.3V_1") (pintype "passive"))
      (node (ref "H2") (pin "2") (pinfunction "-3.3V_2") (pintype "passive"))
      (node (ref "L3") (pin "2") (pinfunction "2_2") (pintype "passive"))
      (node (ref "R11") (pin "2") (pinfunction "2_2") (pintype "passive"))
      (node (ref "R7") (pin "2") (pinfunction "2_2") (pintype "passive"))
    )
    (net (code "7") (name "Net-(C19-Pad1)") (class "Default")
      (node (ref "C19") (pin "1") (pinfunction "1_1") (pintype "passive"))
      (node (ref "R9") (pin "2") (pinfunction "2_2") (pintype "passive"))
    )
    (net (code "8") (name "Net-(C21-Pad1)") (class "Default")
      (node (ref "C21") (pin "1") (pinfunction "1_1") (pintype "passive"))
      (node (ref "R12") (pin "2") (pinfunction "2_2") (pintype "passive"))
    )
    (net (code "9") (name "Net-(C26-Pad2)") (class "Default")
      (node (ref "C26") (pin "2") (pinfunction "2_2") (pintype "passive"))
      (node (ref "C27") (pin "2") (pinfunction "2_2") (pintype "passive"))
      (node (ref "C28") (pin "2") (pinfunction "2_2") (pintype "passive"))
      (node (ref "CN4") (pin "1") (pinfunction "5V_1") (pintype "passive"))
      (node (ref "CN4") (pin "2") (pinfunction "5V_2") (pintype "passive"))
      (node (ref "H4") (pin "1") (pinfunction "-3.3V_1") (pintype "passive"))
      (node (ref "H4") (pin "2") (pinfunction "-3.3V_2") (pintype "passive"))
      (node (ref "L4") (pin "2") (pinfunction "2_2") (pintype "passive"))
      (node (ref "R14") (pin "2") (pinfunction "2_2") (pintype "passive"))
      (node (ref "R15") (pin "2") (pinfunction "2_2") (pintype "passive"))
    )
    (net (code "10") (name "Net-(C29-Pad1)") (class "Default")
      (node (ref "C29") (pin "1") (pinfunction "1_1") (pintype "passive"))
      (node (ref "R16") (pin "2") (pinfunction "2_2") (pintype "passive"))
    )
    (net (code "11") (name "Net-(C33-Pad2)") (class "Default")
      (node (ref "C33") (pin "2") (pinfunction "2_2") (pintype "passive"))
      (node (ref "C34") (pin "2") (pinfunction "2_2") (pintype "passive"))
      (node (ref "C35") (pin "2") (pinfunction "2_2") (pintype "passive"))
      (node (ref "CN5") (pin "3") (pinfunction "GND_3") (pintype "passive"))
      (node (ref "CN5") (pin "4") (pinfunction "GND_4") (pintype "passive"))
      (node (ref "H5") (pin "3") (pinfunction "GND_3") (pintype "passive"))
      (node (ref "H5") (pin "4") (pinfunction "GND_4") (pintype "passive"))
      (node (ref "L5") (pin "2") (pinfunction "2_2") (pintype "passive"))
      (node (ref "R18") (pin "2") (pinfunction "2_2") (pintype "passive"))
      (node (ref "R19") (pin "2") (pinfunction "2_2") (pintype "passive"))
    )
    (net (code "12") (name "Net-(C36-Pad1)") (class "Default")
      (node (ref "C36") (pin "1") (pinfunction "1_1") (pintype "passive"))
      (node (ref "R21") (pin "2") (pinfunction "2_2") (pintype "passive"))
    )
    (net (code "13") (name "Net-(C38-Pad2)") (class "Default")
      (node (ref "C38") (pin "2") (pinfunction "2_2") (pintype "passive"))
      (node (ref "C39") (pin "2") (pinfunction "2_2") (pintype "passive"))
      (node (ref "C40") (pin "2") (pinfunction "2_2") (pintype "passive"))
      (node (ref "CN6") (pin "3") (pinfunction "GND_3") (pintype "passive"))
      (node (ref "CN6") (pin "4") (pinfunction "GND_4") (pintype "passive"))
      (node (ref "H6") (pin "3") (pinfunction "GND_3") (pintype "passive"))
      (node (ref "H6") (pin "4") (pinfunction "GND_4") (pintype "passive"))
      (node (ref "L6") (pin "2") (pinfunction "2_2") (pintype "passive"))
      (node (ref "R20") (pin "2") (pinfunction "2_2") (pintype "passive"))
      (node (ref "R23") (pin "2") (pinfunction "2_2") (pintype "passive"))
    )
    (net (code "14") (name "Net-(C43-Pad1)") (class "Default")
      (node (ref "C43") (pin "1") (pinfunction "1_1") (pintype "passive"))
      (node (ref "R24") (pin "2") (pinfunction "2_2") (pintype "passive"))
    )
    (net (code "15") (name "Net-(D1-K)") (class "Default")
      (node (ref "C1") (pin "2") (pinfunction "2_2") (pintype "passive"))
      (node (ref "D1") (pin "1") (pinfunction "K_1") (pintype "passive"))
      (node (ref "L1") (pin "1") (pinfunction "1_1") (pintype "passive"))
      (node (ref "U1") (pin "8") (pinfunction "PH_8") (pintype "passive"))
    )
    (net (code "16") (name "Net-(D2-K)") (class "Default")
      (node (ref "C11") (pin "2") (pinfunction "2_2") (pintype "passive"))
      (node (ref "D2") (pin "1") (pinfunction "K_1") (pintype "passive"))
      (node (ref "L2") (pin "1") (pinfunction "1_1") (pintype "passive"))
      (node (ref "U2") (pin "8") (pinfunction "PH_8") (pintype "passive"))
    )
    (net (code "17") (name "Net-(D3-K)") (class "Default")
      (node (ref "C15") (pin "2") (pinfunction "2_2") (pintype "passive"))
      (node (ref "D3") (pin "1") (pinfunction "K_1") (pintype "passive"))
      (node (ref "L3") (pin "1") (pinfunction "1_1") (pintype "passive"))
      (node (ref "U3") (pin "8") (pinfunction "PH_8") (pintype "passive"))
    )
    (net (code "18") (name "Net-(D4-K)") (class "Default")
      (node (ref "C25") (pin "2") (pinfunction "2_2") (pintype "passive"))
      (node (ref "D4") (pin "1") (pinfunction "K_1") (pintype "passive"))
      (node (ref "L4") (pin "1") (pinfunction "1_1") (pintype "passive"))
      (node (ref "U4") (pin "8") (pinfunction "PH_8") (pintype "passive"))
    )
    (net (code "19") (name "Net-(D5-K)") (class "Default")
      (node (ref "C32") (pin "2") (pinfunction "2_2") (pintype "passive"))
      (node (ref "D5") (pin "1") (pinfunction "K_1") (pintype "passive"))
      (node (ref "L5") (pin "1") (pinfunction "1_1") (pintype "passive"))
      (node (ref "U5") (pin "8") (pinfunction "PH_8") (pintype "passive"))
    )
    (net (code "20") (name "Net-(D6-K)") (class "Default")
      (node (ref "C37") (pin "2") (pinfunction "2_2") (pintype "passive"))
      (node (ref "D6") (pin "1") (pinfunction "K_1") (pintype "passive"))
      (node (ref "L6") (pin "1") (pinfunction "1_1") (pintype "passive"))
      (node (ref "U6") (pin "8") (pinfunction "PH_8") (pintype "passive"))
    )
    (net (code "21") (name "Net-(DC1-Pad1)") (class "Default")
      (node (ref "DC1") (pin "1") (pinfunction "1_1") (pintype "passive"))
      (node (ref "SW1") (pin "3") (pinfunction "3_3") (pintype "passive"))
    )
    (net (code "22") (name "Net-(LED1-A)") (class "Default")
      (node (ref "LED1") (pin "2") (pinfunction "A_2") (pintype "passive"))
      (node (ref "R1") (pin "1") (pinfunction "1_1") (pintype "passive"))
    )
    (net (code "23") (name "Net-(LED2-A)") (class "Default")
      (node (ref "LED2") (pin "2") (pinfunction "A_2") (pintype "passive"))
      (node (ref "R2") (pin "1") (pinfunction "1_1") (pintype "passive"))
    )
    (net (code "24") (name "Net-(LED3-A)") (class "Default")
      (node (ref "LED3") (pin "2") (pinfunction "A_2") (pintype "passive"))
      (node (ref "R6") (pin "1") (pinfunction "1_1") (pintype "passive"))
    )
    (net (code "25") (name "Net-(LED4-A)") (class "Default")
      (node (ref "LED4") (pin "2") (pinfunction "A_2") (pintype "passive"))
      (node (ref "R7") (pin "1") (pinfunction "1_1") (pintype "passive"))
    )
    (net (code "26") (name "Net-(LED5-A)") (class "Default")
      (node (ref "LED5") (pin "2") (pinfunction "A_2") (pintype "passive"))
      (node (ref "R14") (pin "1") (pinfunction "1_1") (pintype "passive"))
    )
    (net (code "27") (name "Net-(LED6-A)") (class "Default")
      (node (ref "LED6") (pin "2") (pinfunction "A_2") (pintype "passive"))
      (node (ref "R18") (pin "1") (pinfunction "1_1") (pintype "passive"))
    )
    (net (code "28") (name "Net-(LED7-A)") (class "Default")
      (node (ref "LED7") (pin "2") (pinfunction "A_2") (pintype "passive"))
      (node (ref "R20") (pin "1") (pinfunction "1_1") (pintype "passive"))
    )
    (net (code "29") (name "Net-(U1-BOOT)") (class "Default")
      (node (ref "C1") (pin "1") (pinfunction "1_1") (pintype "passive"))
      (node (ref "U1") (pin "1") (pinfunction "BOOT_1") (pintype "passive"))
    )
    (net (code "30") (name "Net-(U1-COMP)") (class "Default")
      (node (ref "C10") (pin "2") (pinfunction "2_2") (pintype "passive"))
      (node (ref "C5") (pin "2") (pinfunction "2_2") (pintype "passive"))
      (node (ref "U1") (pin "6") (pinfunction "COMP_6") (pintype "passive"))
    )
    (net (code "31") (name "Net-(U1-SS)") (class "Default")
      (node (ref "C9") (pin "2") (pinfunction "2_2") (pintype "passive"))
      (node (ref "U1") (pin "4") (pinfunction "SS_4") (pintype "passive"))
    )
    (net (code "32") (name "Net-(U1-VSENSE)") (class "Default")
      (node (ref "R3") (pin "1") (pinfunction "1_1") (pintype "passive"))
      (node (ref "R5") (pin "2") (pinfunction "2_2") (pintype "passive"))
      (node (ref "U1") (pin "5") (pinfunction "VSENSE_5") (pintype "passive"))
    )
    (net (code "33") (name "Net-(U2-BOOT)") (class "Default")
      (node (ref "C11") (pin "1") (pinfunction "1_1") (pintype "passive"))
      (node (ref "U2") (pin "1") (pinfunction "BOOT_1") (pintype "passive"))
    )
    (net (code "34") (name "Net-(U2-COMP)") (class "Default")
      (node (ref "C19") (pin "2") (pinfunction "2_2") (pintype "passive"))
      (node (ref "C22") (pin "2") (pinfunction "2_2") (pintype "passive"))
      (node (ref "U2") (pin "6") (pinfunction "COMP_6") (pintype "passive"))
    )
    (net (code "35") (name "Net-(U2-SS)") (class "Default")
      (node (ref "C20") (pin "2") (pinfunction "2_2") (pintype "passive"))
      (node (ref "U2") (pin "4") (pinfunction "SS_4") (pintype "passive"))
    )
    (net (code "36") (name "Net-(U2-VSENSE)") (class "Default")
      (node (ref "R10") (pin "2") (pinfunction "2_2") (pintype "passive"))
      (node (ref "R8") (pin "1") (pinfunction "1_1") (pintype "passive"))
      (node (ref "U2") (pin "5") (pinfunction "VSENSE_5") (pintype "passive"))
    )
    (net (code "37") (name "Net-(U3-BOOT)") (class "Default")
      (node (ref "C15") (pin "1") (pinfunction "1_1") (pintype "passive"))
      (node (ref "U3") (pin "1") (pinfunction "BOOT_1") (pintype "passive"))
    )
    (net (code "38") (name "Net-(U3-COMP)") (class "Default")
      (node (ref "C21") (pin "2") (pinfunction "2_2") (pintype "passive"))
      (node (ref "C24") (pin "2") (pinfunction "2_2") (pintype "passive"))
      (node (ref "U3") (pin "6") (pinfunction "COMP_6") (pintype "passive"))
    )
    (net (code "39") (name "Net-(U3-SS)") (class "Default")
      (node (ref "C23") (pin "2") (pinfunction "2_2") (pintype "passive"))
      (node (ref "U3") (pin "4") (pinfunction "SS_4") (pintype "passive"))
    )
    (net (code "40") (name "Net-(U3-VSENSE)") (class "Default")
      (node (ref "R11") (pin "1") (pinfunction "1_1") (pintype "passive"))
      (node (ref "R13") (pin "2") (pinfunction "2_2") (pintype "passive"))
      (node (ref "U3") (pin "5") (pinfunction "VSENSE_5") (pintype "passive"))
    )
    (net (code "41") (name "Net-(U4-BOOT)") (class "Default")
      (node (ref "C25") (pin "1") (pinfunction "1_1") (pintype "passive"))
      (node (ref "U4") (pin "1") (pinfunction "BOOT_1") (pintype "passive"))
    )
    (net (code "42") (name "Net-(U4-COMP)") (class "Default")
      (node (ref "C29") (pin "2") (pinfunction "2_2") (pintype "passive"))
      (node (ref "C31") (pin "2") (pinfunction "2_2") (pintype "passive"))
      (node (ref "U4") (pin "6") (pinfunction "COMP_6") (pintype "passive"))
    )
    (net (code "43") (name "Net-(U4-SS)") (class "Default")
      (node (ref "C30") (pin "2") (pinfunction "2_2") (pintype "passive"))
      (node (ref "U4") (pin "4") (pinfunction "SS_4") (pintype "passive"))
    )
    (net (code "44") (name "Net-(U4-VSENSE)") (class "Default")
      (node (ref "R15") (pin "1") (pinfunction "1_1") (pintype "passive"))
      (node (ref "R17") (pin "2") (pinfunction "2_2") (pintype "passive"))
      (node (ref "U4") (pin "5") (pinfunction "VSENSE_5") (pintype "passive"))
    )
    (net (code "45") (name "Net-(U5-BOOT)") (class "Default")
      (node (ref "C32") (pin "1") (pinfunction "1_1") (pintype "passive"))
      (node (ref "U5") (pin "1") (pinfunction "BOOT_1") (pintype "passive"))
    )
    (net (code "46") (name "Net-(U5-COMP)") (class "Default")
      (node (ref "C36") (pin "2") (pinfunction "2_2") (pintype "passive"))
      (node (ref "C42") (pin "2") (pinfunction "2_2") (pintype "passive"))
      (node (ref "U5") (pin "6") (pinfunction "COMP_6") (pintype "passive"))
    )
    (net (code "47") (name "Net-(U5-SS)") (class "Default")
      (node (ref "C41") (pin "2") (pinfunction "2_2") (pintype "passive"))
      (node (ref "U5") (pin "4") (pinfunction "SS_4") (pintype "passive"))
    )
    (net (code "48") (name "Net-(U5-VSENSE)") (class "Default")
      (node (ref "R19") (pin "1") (pinfunction "1_1") (pintype "passive"))
      (node (ref "R22") (pin "2") (pinfunction "2_2") (pintype "passive"))
      (node (ref "U5") (pin "5") (pinfunction "VSENSE_5") (pintype "passive"))
    )
    (net (code "49") (name "Net-(U6-BOOT)") (class "Default")
      (node (ref "C37") (pin "1") (pinfunction "1_1") (pintype "passive"))
      (node (ref "U6") (pin "1") (pinfunction "BOOT_1") (pintype "passive"))
    )
    (net (code "50") (name "Net-(U6-COMP)") (class "Default")
      (node (ref "C43") (pin "2") (pinfunction "2_2") (pintype "passive"))
      (node (ref "C45") (pin "2") (pinfunction "2_2") (pintype "passive"))
      (node (ref "U6") (pin "6") (pinfunction "COMP_6") (pintype "passive"))
    )
    (net (code "51") (name "Net-(U6-SS)") (class "Default")
      (node (ref "C44") (pin "2") (pinfunction "2_2") (pintype "passive"))
      (node (ref "U6") (pin "4") (pinfunction "SS_4") (pintype "passive"))
    )
    (net (code "52") (name "Net-(U6-VSENSE)") (class "Default")
      (node (ref "R23") (pin "1") (pinfunction "1_1") (pintype "passive"))
      (node (ref "R25") (pin "2") (pinfunction "2_2") (pintype "passive"))
      (node (ref "U6") (pin "5") (pinfunction "VSENSE_5") (pintype "passive"))
    )
    (net (code "53") (name "unconnected-(SW1-Pad1)") (class "Default")
      (node (ref "SW1") (pin "1") (pinfunction "1_1") (pintype "passive"))
    )
    (net (code "54") (name "unconnected-(U1-EN-Pad3)") (class "Default")
      (node (ref "U1") (pin "3") (pinfunction "EN_3") (pintype "passive"))
    )
    (net (code "55") (name "unconnected-(U2-EN-Pad3)") (class "Default")
      (node (ref "U2") (pin "3") (pinfunction "EN_3") (pintype "passive"))
    )
    (net (code "56") (name "unconnected-(U3-EN-Pad3)") (class "Default")
      (node (ref "U3") (pin "3") (pinfunction "EN_3") (pintype "passive"))
    )
    (net (code "57") (name "unconnected-(U4-EN-Pad3)") (class "Default")
      (node (ref "U4") (pin "3") (pinfunction "EN_3") (pintype "passive"))
    )
    (net (code "58") (name "unconnected-(U5-EN-Pad3)") (class "Default")
      (node (ref "U5") (pin "3") (pinfunction "EN_3") (pintype "passive"))
    )
    (net (code "59") (name "unconnected-(U6-EN-Pad3)") (class "Default")
      (node (ref "U6") (pin "3") (pinfunction "EN_3") (pintype "passive"))
    )
  )
)
